# CLKB_main.net
KiCad netlist of a schematic drawn in Altium Designer
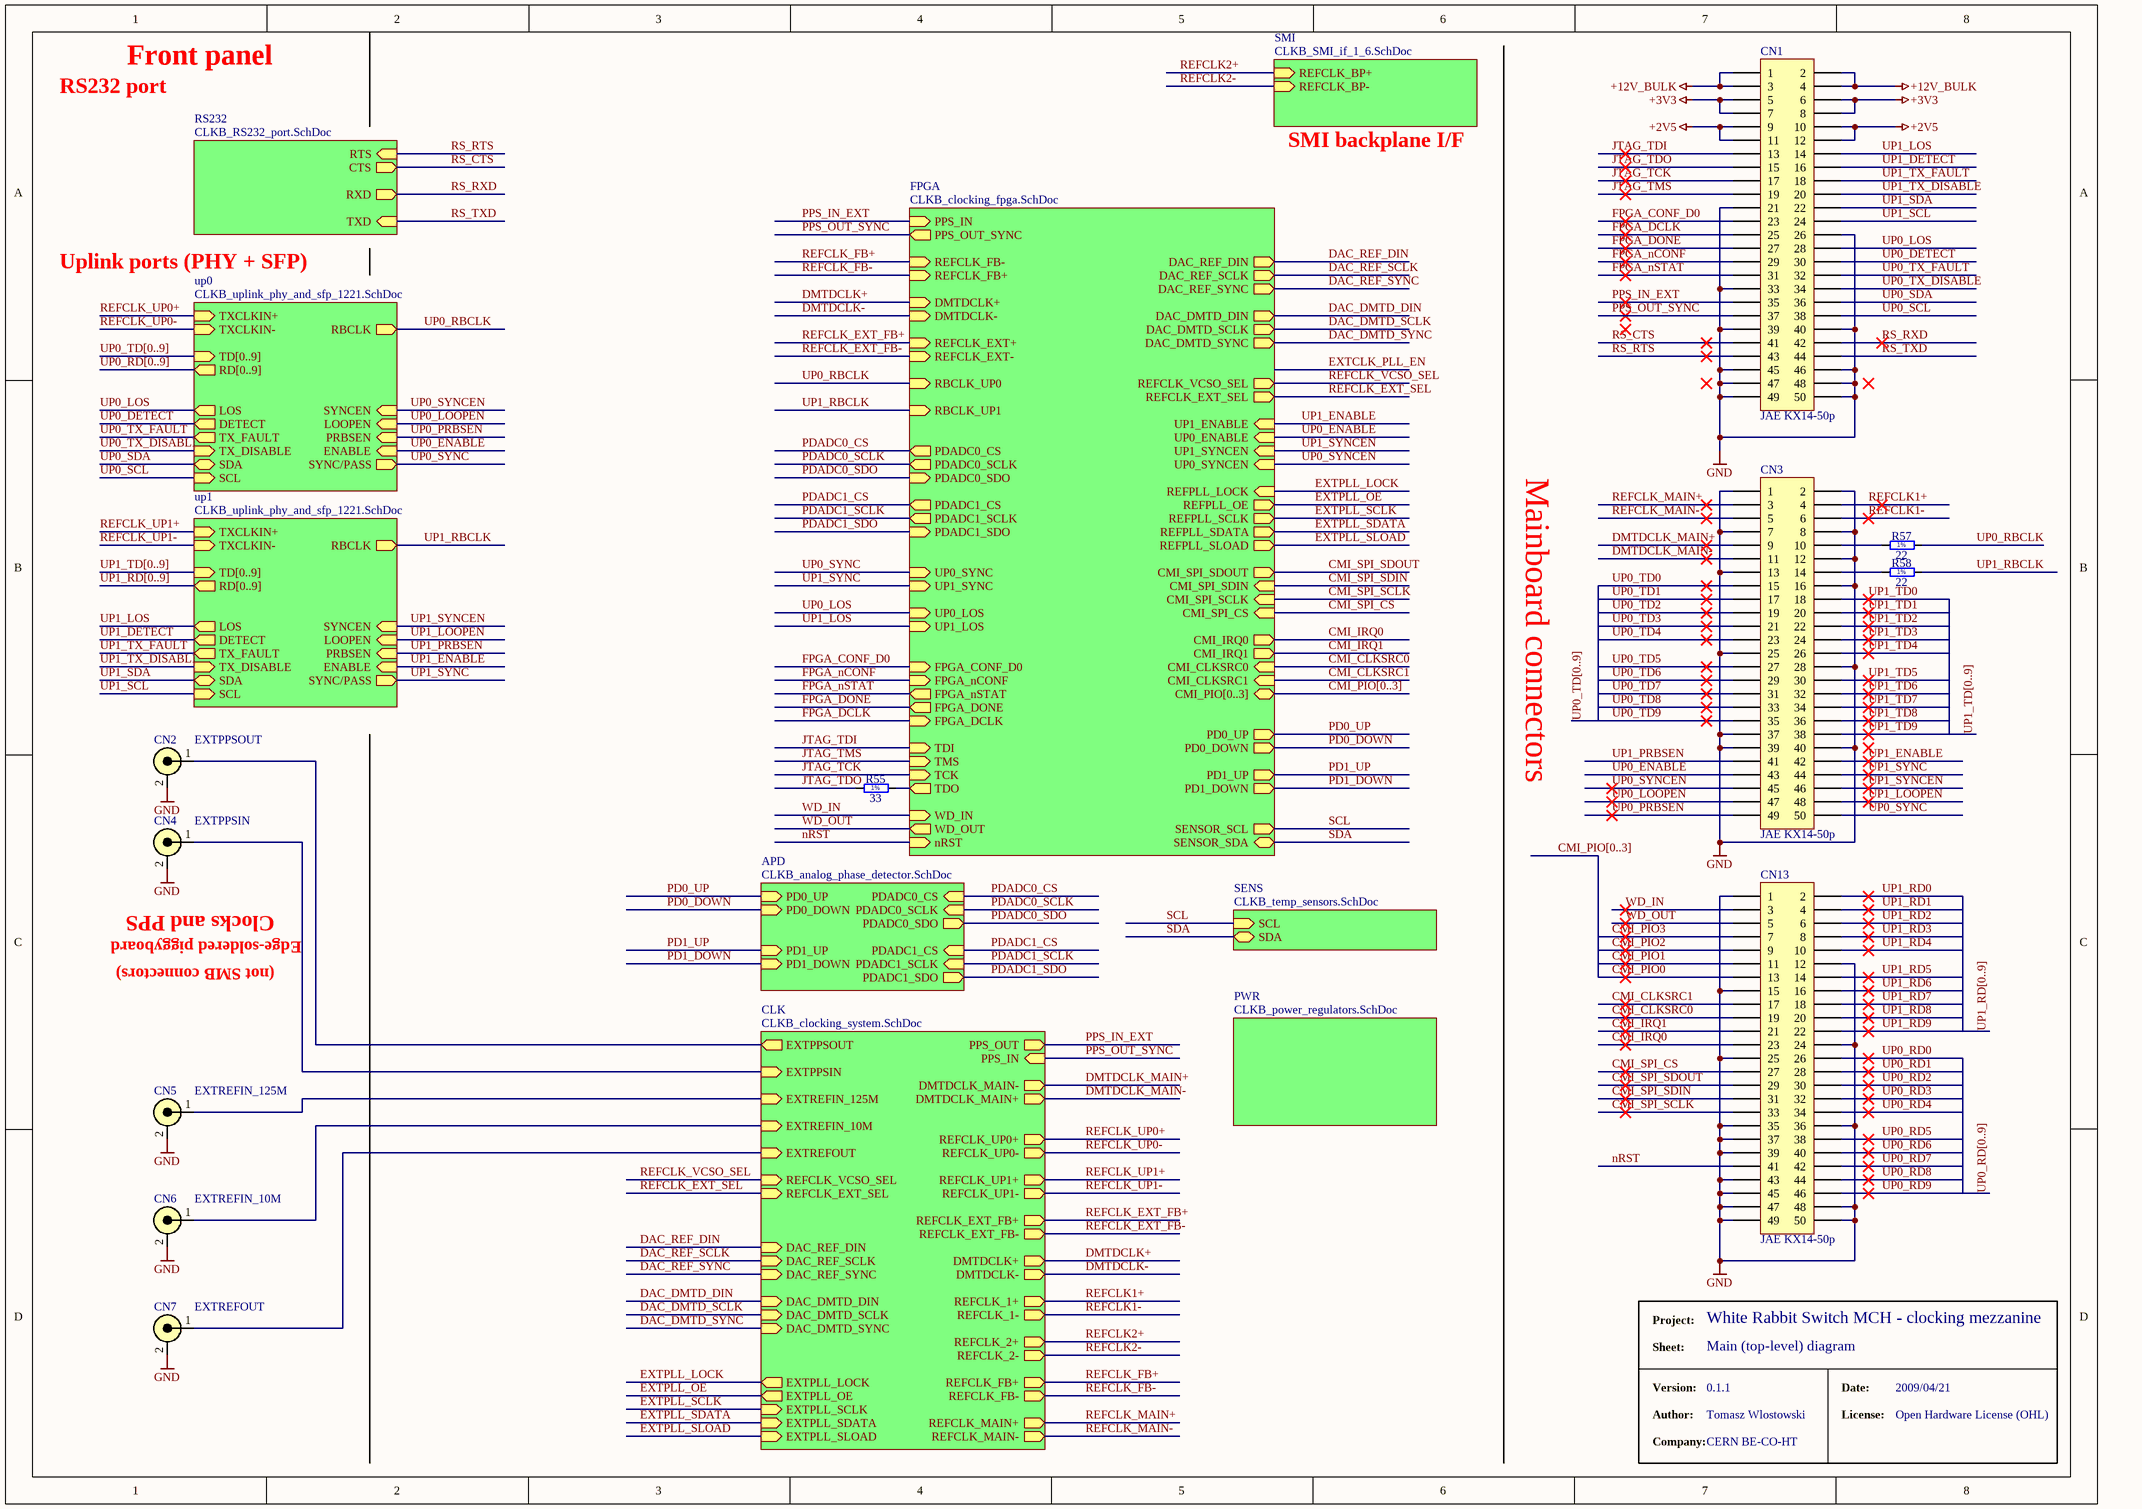
[diagram p0: CLKB_main.SchDoc]

(export (version "E")
  (design (tool "Eeschema 10.0.6"))
  (components
    (comp (ref "CN1")
      (value "JAE KX14-50p")
      (footprint "JAE_KX14_50P")
      (description "multipin B2B connector (plug)")
      (libsource (lib "wr_switch") (part "KX14_50p"))
    )
    (comp (ref "CN2")
      (value "EXTPPSOUT")
      (footprint "MCH_SPECIAL_FP_CLOCKS")
      (description "SMB piggyboard connection")
      (libsource (lib "wr_switch") (part "SMA_SOCKET"))
    )
    (comp (ref "CN3")
      (value "JAE KX14-50p")
      (footprint "JAE_KX14_50P")
      (description "multipin B2B connector (plug)")
      (libsource (lib "wr_switch") (part "KX14_50p"))
    )
    (comp (ref "CN4")
      (value "EXTPPSIN")
      (footprint "MCH_SPECIAL_FP_CLOCKS")
      (description "SMB piggyboard connection")
      (libsource (lib "wr_switch") (part "SMA_SOCKET"))
    )
    (comp (ref "CN5")
      (value "EXTREFIN_125M")
      (footprint "MCH_SPECIAL_FP_CLOCKS")
      (description "SMB piggyboard connection")
      (libsource (lib "wr_switch") (part "SMA_SOCKET"))
    )
    (comp (ref "CN6")
      (value "EXTREFIN_10M")
      (footprint "MCH_SPECIAL_FP_CLOCKS")
      (description "SMB piggyboard connection")
      (libsource (lib "wr_switch") (part "SMA_SOCKET"))
    )
    (comp (ref "CN7")
      (value "EXTREFOUT")
      (footprint "MCH_SPECIAL_FP_CLOCKS")
      (description "SMB piggyboard connection")
      (libsource (lib "wr_switch") (part "SMA_SOCKET"))
    )
    (comp (ref "CN13")
      (value "JAE KX14-50p")
      (footprint "JAE_KX14_50P")
      (description "multipin B2B connector (plug)")
      (libsource (lib "wr_switch") (part "KX14_50p"))
    )
    (comp (ref "R55")
      (value "33")
      (footprint "RESC1608X55N")
      (description "Resistor - 1%")
      (fields
        (field (name "PART NUMBER") "R0603_33R_1%_0.1W_100PPM")
        (field (name "POWER") "0.1W")
        (field (name "AUTHOR") "CERN DEM JLC")
      )
      (libsource (lib "Resistors") (part "Resistor - 1%"))
    )
    (comp (ref "R57")
      (value "22")
      (footprint "RESC1608X55N")
      (description "Resistor - 1%")
      (fields
        (field (name "PART NUMBER") "R0603_22R_1%_0.1W_100PPM")
        (field (name "POWER") "0.1W")
        (field (name "AUTHOR") "CERN DEM JLC")
      )
      (libsource (lib "Resistors") (part "Resistor - 1%"))
    )
    (comp (ref "R58")
      (value "22")
      (footprint "RESC1608X55N")
      (description "Resistor - 1%")
      (fields
        (field (name "PART NUMBER") "R0603_22R_1%_0.1W_100PPM")
        (field (name "POWER") "0.1W")
        (field (name "AUTHOR") "CERN DEM JLC")
      )
      (libsource (lib "Resistors") (part "Resistor - 1%"))
    )
  )
  (nets
    (net (code "1") (name "+2V5") (class "Default")
      (node (ref "CN1") (pin "10") (pinfunction "10_10") (pintype "passive"))
      (node (ref "CN1") (pin "11") (pinfunction "11_11") (pintype "passive"))
      (node (ref "CN1") (pin "12") (pinfunction "12_12") (pintype "passive"))
      (node (ref "CN1") (pin "9") (pinfunction "9_9") (pintype "passive"))
    )
    (net (code "2") (name "+3V3") (class "Default")
      (node (ref "CN1") (pin "5") (pinfunction "5_5") (pintype "passive"))
      (node (ref "CN1") (pin "6") (pinfunction "6_6") (pintype "passive"))
      (node (ref "CN1") (pin "7") (pinfunction "7_7") (pintype "passive"))
      (node (ref "CN1") (pin "8") (pinfunction "8_8") (pintype "passive"))
    )
    (net (code "3") (name "+12V_BULK") (class "Default")
      (node (ref "CN1") (pin "1") (pinfunction "1_1") (pintype "passive"))
      (node (ref "CN1") (pin "2") (pinfunction "2_2") (pintype "passive"))
      (node (ref "CN1") (pin "3") (pinfunction "3_3") (pintype "passive"))
      (node (ref "CN1") (pin "4") (pinfunction "4_4") (pintype "passive"))
    )
    (net (code "4") (name "/CMI_CLKSRC0") (class "Default")
      (node (ref "CN13") (pin "19") (pinfunction "19_19") (pintype "passive"))
    )
    (net (code "5") (name "/CMI_CLKSRC1") (class "Default")
      (node (ref "CN13") (pin "17") (pinfunction "17_17") (pintype "passive"))
    )
    (net (code "6") (name "/CMI_IRQ0") (class "Default")
      (node (ref "CN13") (pin "23") (pinfunction "23_23") (pintype "passive"))
    )
    (net (code "7") (name "/CMI_IRQ1") (class "Default")
      (node (ref "CN13") (pin "21") (pinfunction "21_21") (pintype "passive"))
    )
    (net (code "8") (name "/CMI_PIO0") (class "Default")
      (node (ref "CN13") (pin "13") (pinfunction "13_13") (pintype "passive"))
    )
    (net (code "9") (name "/CMI_PIO1") (class "Default")
      (node (ref "CN13") (pin "11") (pinfunction "11_11") (pintype "passive"))
    )
    (net (code "10") (name "/CMI_PIO2") (class "Default")
      (node (ref "CN13") (pin "9") (pinfunction "9_9") (pintype "passive"))
    )
    (net (code "11") (name "/CMI_PIO3") (class "Default")
      (node (ref "CN13") (pin "7") (pinfunction "7_7") (pintype "passive"))
    )
    (net (code "13") (name "/CMI_SPI_CS") (class "Default")
      (node (ref "CN13") (pin "27") (pinfunction "27_27") (pintype "passive"))
    )
    (net (code "14") (name "/CMI_SPI_SCLK") (class "Default")
      (node (ref "CN13") (pin "33") (pinfunction "33_33") (pintype "passive"))
    )
    (net (code "15") (name "/CMI_SPI_SDIN") (class "Default")
      (node (ref "CN13") (pin "31") (pinfunction "31_31") (pintype "passive"))
    )
    (net (code "16") (name "/CMI_SPI_SDOUT") (class "Default")
      (node (ref "CN13") (pin "29") (pinfunction "29_29") (pintype "passive"))
    )
    (net (code "25") (name "/DMTDCLK_MAIN+") (class "Default")
      (node (ref "CN3") (pin "9") (pinfunction "9_9") (pintype "passive"))
    )
    (net (code "26") (name "/DMTDCLK_MAIN-") (class "Default")
      (node (ref "CN3") (pin "11") (pinfunction "11_11") (pintype "passive"))
    )
    (net (code "33") (name "/EXTPPSIN") (class "Default")
      (node (ref "CN4") (pin "1") (pinfunction "HOT_1") (pintype "passive"))
    )
    (net (code "34") (name "/EXTPPSOUT") (class "Default")
      (node (ref "CN2") (pin "1") (pinfunction "HOT_1") (pintype "passive"))
    )
    (net (code "35") (name "/EXTREFIN_10M") (class "Default")
      (node (ref "CN6") (pin "1") (pinfunction "HOT_1") (pintype "passive"))
    )
    (net (code "36") (name "/EXTREFIN_125M") (class "Default")
      (node (ref "CN5") (pin "1") (pinfunction "HOT_1") (pintype "passive"))
    )
    (net (code "37") (name "/EXTREFOUT") (class "Default")
      (node (ref "CN7") (pin "1") (pinfunction "HOT_1") (pintype "passive"))
    )
    (net (code "38") (name "/FPGA_CONF_D0") (class "Default")
      (node (ref "CN1") (pin "23") (pinfunction "23_23") (pintype "passive"))
    )
    (net (code "39") (name "/FPGA_DCLK") (class "Default")
      (node (ref "CN1") (pin "25") (pinfunction "25_25") (pintype "passive"))
    )
    (net (code "40") (name "/FPGA_DONE") (class "Default")
      (node (ref "CN1") (pin "27") (pinfunction "27_27") (pintype "passive"))
    )
    (net (code "41") (name "/FPGA_nCONF") (class "Default")
      (node (ref "CN1") (pin "29") (pinfunction "29_29") (pintype "passive"))
    )
    (net (code "42") (name "/FPGA_nSTAT") (class "Default")
      (node (ref "CN1") (pin "31") (pinfunction "31_31") (pintype "passive"))
    )
    (net (code "43") (name "/JTAG_TCK") (class "Default")
      (node (ref "CN1") (pin "17") (pinfunction "17_17") (pintype "passive"))
    )
    (net (code "44") (name "/JTAG_TDI") (class "Default")
      (node (ref "CN1") (pin "13") (pinfunction "13_13") (pintype "passive"))
    )
    (net (code "45") (name "/JTAG_TDO") (class "Default")
      (node (ref "CN1") (pin "15") (pinfunction "15_15") (pintype "passive"))
      (node (ref "R55") (pin "1") (pinfunction "1_1") (pintype "passive"))
    )
    (net (code "46") (name "/JTAG_TMS") (class "Default")
      (node (ref "CN1") (pin "19") (pinfunction "19_19") (pintype "passive"))
    )
    (net (code "57") (name "/PPS_IN_EXT") (class "Default")
      (node (ref "CN1") (pin "35") (pinfunction "35_35") (pintype "passive"))
    )
    (net (code "58") (name "/PPS_OUT_SYNC") (class "Default")
      (node (ref "CN1") (pin "37") (pinfunction "37_37") (pintype "passive"))
    )
    (net (code "59") (name "/REFCLK1+") (class "Default")
      (node (ref "CN3") (pin "4") (pinfunction "4_4") (pintype "passive"))
    )
    (net (code "68") (name "/REFCLK1-") (class "Default")
      (node (ref "CN3") (pin "6") (pinfunction "6_6") (pintype "passive"))
    )
    (net (code "69") (name "/REFCLK_MAIN+") (class "Default")
      (node (ref "CN3") (pin "3") (pinfunction "3_3") (pintype "passive"))
    )
    (net (code "75") (name "/REFCLK_MAIN-") (class "Default")
      (node (ref "CN3") (pin "5") (pinfunction "5_5") (pintype "passive"))
    )
    (net (code "76") (name "/RS_CTS") (class "Default")
      (node (ref "CN1") (pin "41") (pinfunction "41_41") (pintype "passive"))
    )
    (net (code "78") (name "/RS_RTS") (class "Default")
      (node (ref "CN1") (pin "43") (pinfunction "43_43") (pintype "passive"))
    )
    (net (code "81") (name "/RS_RXD") (class "Default")
      (node (ref "CN1") (pin "42") (pinfunction "42_42") (pintype "passive"))
    )
    (net (code "82") (name "/RS_TXD") (class "Default")
      (node (ref "CN1") (pin "44") (pinfunction "44_44") (pintype "passive"))
    )
    (net (code "83") (name "/TDO") (class "Default")
      (node (ref "R55") (pin "2") (pinfunction "2_2") (pintype "passive"))
    )
    (net (code "85") (name "/UP0_DETECT") (class "Default")
      (node (ref "CN1") (pin "30") (pinfunction "30_30") (pintype "passive"))
    )
    (net (code "87") (name "/UP0_ENABLE") (class "Default")
      (node (ref "CN3") (pin "43") (pinfunction "43_43") (pintype "passive"))
    )
    (net (code "88") (name "/UP0_LOOPEN") (class "Default")
      (node (ref "CN3") (pin "47") (pinfunction "47_47") (pintype "passive"))
    )
    (net (code "89") (name "/UP0_LOS") (class "Default")
      (node (ref "CN1") (pin "28") (pinfunction "28_28") (pintype "passive"))
    )
    (net (code "90") (name "/UP0_PRBSEN") (class "Default")
      (node (ref "CN3") (pin "49") (pinfunction "49_49") (pintype "passive"))
    )
    (net (code "91") (name "/UP0_RBCLK") (class "Default")
      (node (ref "R57") (pin "2") (pinfunction "2_2") (pintype "passive"))
    )
    (net (code "92") (name "/UP0_RD0") (class "Default")
      (node (ref "CN13") (pin "26") (pinfunction "26_26") (pintype "passive"))
    )
    (net (code "93") (name "/UP0_RD1") (class "Default")
      (node (ref "CN13") (pin "28") (pinfunction "28_28") (pintype "passive"))
    )
    (net (code "94") (name "/UP0_RD2") (class "Default")
      (node (ref "CN13") (pin "30") (pinfunction "30_30") (pintype "passive"))
    )
    (net (code "95") (name "/UP0_RD3") (class "Default")
      (node (ref "CN13") (pin "32") (pinfunction "32_32") (pintype "passive"))
    )
    (net (code "96") (name "/UP0_RD4") (class "Default")
      (node (ref "CN13") (pin "34") (pinfunction "34_34") (pintype "passive"))
    )
    (net (code "97") (name "/UP0_RD5") (class "Default")
      (node (ref "CN13") (pin "38") (pinfunction "38_38") (pintype "passive"))
    )
    (net (code "99") (name "/UP0_RD6") (class "Default")
      (node (ref "CN13") (pin "40") (pinfunction "40_40") (pintype "passive"))
    )
    (net (code "100") (name "/UP0_RD7") (class "Default")
      (node (ref "CN13") (pin "42") (pinfunction "42_42") (pintype "passive"))
    )
    (net (code "101") (name "/UP0_RD8") (class "Default")
      (node (ref "CN13") (pin "44") (pinfunction "44_44") (pintype "passive"))
    )
    (net (code "103") (name "/UP0_RD9") (class "Default")
      (node (ref "CN13") (pin "46") (pinfunction "46_46") (pintype "passive"))
    )
    (net (code "104") (name "/UP0_SCL") (class "Default")
      (node (ref "CN1") (pin "38") (pinfunction "38_38") (pintype "passive"))
    )
    (net (code "105") (name "/UP0_SDA") (class "Default")
      (node (ref "CN1") (pin "36") (pinfunction "36_36") (pintype "passive"))
    )
    (net (code "106") (name "/UP0_SYNC") (class "Default")
      (node (ref "CN3") (pin "50") (pinfunction "50_50") (pintype "passive"))
    )
    (net (code "107") (name "/UP0_SYNCEN") (class "Default")
      (node (ref "CN3") (pin "45") (pinfunction "45_45") (pintype "passive"))
    )
    (net (code "108") (name "/UP0_TD0") (class "Default")
      (node (ref "CN3") (pin "15") (pinfunction "15_15") (pintype "passive"))
    )
    (net (code "109") (name "/UP0_TD1") (class "Default")
      (node (ref "CN3") (pin "17") (pinfunction "17_17") (pintype "passive"))
    )
    (net (code "110") (name "/UP0_TD2") (class "Default")
      (node (ref "CN3") (pin "19") (pinfunction "19_19") (pintype "passive"))
    )
    (net (code "111") (name "/UP0_TD3") (class "Default")
      (node (ref "CN3") (pin "21") (pinfunction "21_21") (pintype "passive"))
    )
    (net (code "112") (name "/UP0_TD4") (class "Default")
      (node (ref "CN3") (pin "23") (pinfunction "23_23") (pintype "passive"))
    )
    (net (code "114") (name "/UP0_TD5") (class "Default")
      (node (ref "CN3") (pin "27") (pinfunction "27_27") (pintype "passive"))
    )
    (net (code "115") (name "/UP0_TD6") (class "Default")
      (node (ref "CN3") (pin "29") (pinfunction "29_29") (pintype "passive"))
    )
    (net (code "116") (name "/UP0_TD7") (class "Default")
      (node (ref "CN3") (pin "31") (pinfunction "31_31") (pintype "passive"))
    )
    (net (code "119") (name "/UP0_TD8") (class "Default")
      (node (ref "CN3") (pin "33") (pinfunction "33_33") (pintype "passive"))
    )
    (net (code "120") (name "/UP0_TD9") (class "Default")
      (node (ref "CN3") (pin "35") (pinfunction "35_35") (pintype "passive"))
    )
    (net (code "121") (name "/UP0_TX_DISABLE") (class "Default")
      (node (ref "CN1") (pin "34") (pinfunction "34_34") (pintype "passive"))
    )
    (net (code "122") (name "/UP0_TX_FAULT") (class "Default")
      (node (ref "CN1") (pin "32") (pinfunction "32_32") (pintype "passive"))
    )
    (net (code "123") (name "/UP1_DETECT") (class "Default")
      (node (ref "CN1") (pin "16") (pinfunction "16_16") (pintype "passive"))
    )
    (net (code "124") (name "/UP1_ENABLE") (class "Default")
      (node (ref "CN3") (pin "42") (pinfunction "42_42") (pintype "passive"))
    )
    (net (code "125") (name "/UP1_LOOPEN") (class "Default")
      (node (ref "CN3") (pin "48") (pinfunction "48_48") (pintype "passive"))
    )
    (net (code "126") (name "/UP1_LOS") (class "Default")
      (node (ref "CN1") (pin "14") (pinfunction "14_14") (pintype "passive"))
    )
    (net (code "127") (name "/UP1_PRBSEN") (class "Default")
      (node (ref "CN3") (pin "41") (pinfunction "41_41") (pintype "passive"))
    )
    (net (code "128") (name "/UP1_RBCLK") (class "Default")
      (node (ref "R58") (pin "2") (pinfunction "2_2") (pintype "passive"))
    )
    (net (code "129") (name "/UP1_RD0") (class "Default")
      (node (ref "CN13") (pin "2") (pinfunction "2_2") (pintype "passive"))
    )
    (net (code "130") (name "/UP1_RD1") (class "Default")
      (node (ref "CN13") (pin "4") (pinfunction "4_4") (pintype "passive"))
    )
    (net (code "131") (name "/UP1_RD2") (class "Default")
      (node (ref "CN13") (pin "6") (pinfunction "6_6") (pintype "passive"))
    )
    (net (code "133") (name "/UP1_RD3") (class "Default")
      (node (ref "CN13") (pin "8") (pinfunction "8_8") (pintype "passive"))
    )
    (net (code "134") (name "/UP1_RD4") (class "Default")
      (node (ref "CN13") (pin "10") (pinfunction "10_10") (pintype "passive"))
    )
    (net (code "148") (name "/UP1_RD5") (class "Default")
      (node (ref "CN13") (pin "14") (pinfunction "14_14") (pintype "passive"))
    )
    (net (code "149") (name "/UP1_RD6") (class "Default")
      (node (ref "CN13") (pin "16") (pinfunction "16_16") (pintype "passive"))
    )
    (net (code "152") (name "/UP1_RD7") (class "Default")
      (node (ref "CN13") (pin "18") (pinfunction "18_18") (pintype "passive"))
    )
    (net (code "153") (name "/UP1_RD8") (class "Default")
      (node (ref "CN13") (pin "20") (pinfunction "20_20") (pintype "passive"))
    )
    (net (code "154") (name "/UP1_RD9") (class "Default")
      (node (ref "CN13") (pin "22") (pinfunction "22_22") (pintype "passive"))
    )
    (net (code "155") (name "/UP1_SCL") (class "Default")
      (node (ref "CN1") (pin "24") (pinfunction "24_24") (pintype "passive"))
    )
    (net (code "156") (name "/UP1_SDA") (class "Default")
      (node (ref "CN1") (pin "22") (pinfunction "22_22") (pintype "passive"))
    )
    (net (code "157") (name "/UP1_SYNC") (class "Default")
      (node (ref "CN3") (pin "44") (pinfunction "44_44") (pintype "passive"))
    )
    (net (code "158") (name "/UP1_SYNCEN") (class "Default")
      (node (ref "CN3") (pin "46") (pinfunction "46_46") (pintype "passive"))
    )
    (net (code "159") (name "/UP1_TD0") (class "Default")
      (node (ref "CN3") (pin "18") (pinfunction "18_18") (pintype "passive"))
    )
    (net (code "160") (name "/UP1_TD1") (class "Default")
      (node (ref "CN3") (pin "20") (pinfunction "20_20") (pintype "passive"))
    )
    (net (code "161") (name "/UP1_TD2") (class "Default")
      (node (ref "CN3") (pin "22") (pinfunction "22_22") (pintype "passive"))
    )
    (net (code "162") (name "/UP1_TD3") (class "Default")
      (node (ref "CN3") (pin "24") (pinfunction "24_24") (pintype "passive"))
    )
    (net (code "163") (name "/UP1_TD4") (class "Default")
      (node (ref "CN3") (pin "26") (pinfunction "26_26") (pintype "passive"))
    )
    (net (code "164") (name "/UP1_TD5") (class "Default")
      (node (ref "CN3") (pin "30") (pinfunction "30_30") (pintype "passive"))
    )
    (net (code "165") (name "/UP1_TD6") (class "Default")
      (node (ref "CN3") (pin "32") (pinfunction "32_32") (pintype "passive"))
    )
    (net (code "166") (name "/UP1_TD7") (class "Default")
      (node (ref "CN3") (pin "34") (pinfunction "34_34") (pintype "passive"))
    )
    (net (code "167") (name "/UP1_TD8") (class "Default")
      (node (ref "CN3") (pin "36") (pinfunction "36_36") (pintype "passive"))
    )
    (net (code "168") (name "/UP1_TD9") (class "Default")
      (node (ref "CN3") (pin "38") (pinfunction "38_38") (pintype "passive"))
    )
    (net (code "169") (name "/UP1_TX_DISABLE") (class "Default")
      (node (ref "CN1") (pin "20") (pinfunction "20_20") (pintype "passive"))
    )
    (net (code "170") (name "/UP1_TX_FAULT") (class "Default")
      (node (ref "CN1") (pin "18") (pinfunction "18_18") (pintype "passive"))
    )
    (net (code "171") (name "/WD_IN") (class "Default")
      (node (ref "CN13") (pin "3") (pinfunction "3_3") (pintype "passive"))
    )
    (net (code "172") (name "/WD_OUT") (class "Default")
      (node (ref "CN13") (pin "5") (pinfunction "5_5") (pintype "passive"))
    )
    (net (code "173") (name "/nRST") (class "Default")
      (node (ref "CN13") (pin "41") (pinfunction "41_41") (pintype "passive"))
    )
    (net (code "174") (name "GND") (class "Default")
      (node (ref "CN1") (pin "21") (pinfunction "21_21") (pintype "passive"))
      (node (ref "CN1") (pin "26") (pinfunction "26_26") (pintype "passive"))
      (node (ref "CN1") (pin "33") (pinfunction "33_33") (pintype "passive"))
      (node (ref "CN1") (pin "39") (pinfunction "39_39") (pintype "passive"))
      (node (ref "CN1") (pin "40") (pinfunction "40_40") (pintype "passive"))
      (node (ref "CN1") (pin "45") (pinfunction "45_45") (pintype "passive"))
      (node (ref "CN1") (pin "46") (pinfunction "46_46") (pintype "passive"))
      (node (ref "CN1") (pin "47") (pinfunction "47_47") (pintype "passive"))
      (node (ref "CN1") (pin "48") (pinfunction "48_48") (pintype "passive"))
      (node (ref "CN1") (pin "49") (pinfunction "49_49") (pintype "passive"))
      (node (ref "CN1") (pin "50") (pinfunction "50_50") (pintype "passive"))
      (node (ref "CN13") (pin "1") (pinfunction "1_1") (pintype "passive"))
      (node (ref "CN13") (pin "12") (pinfunction "12_12") (pintype "passive"))
      (node (ref "CN13") (pin "15") (pinfunction "15_15") (pintype "passive"))
      (node (ref "CN13") (pin "24") (pinfunction "24_24") (pintype "passive"))
      (node (ref "CN13") (pin "25") (pinfunction "25_25") (pintype "passive"))
      (node (ref "CN13") (pin "35") (pinfunction "35_35") (pintype "passive"))
      (node (ref "CN13") (pin "36") (pinfunction "36_36") (pintype "passive"))
      (node (ref "CN13") (pin "37") (pinfunction "37_37") (pintype "passive"))
      (node (ref "CN13") (pin "39") (pinfunction "39_39") (pintype "passive"))
      (node (ref "CN13") (pin "43") (pinfunction "43_43") (pintype "passive"))
      (node (ref "CN13") (pin "45") (pinfunction "45_45") (pintype "passive"))
      (node (ref "CN13") (pin "47") (pinfunction "47_47") (pintype "passive"))
      (node (ref "CN13") (pin "48") (pinfunction "48_48") (pintype "passive"))
      (node (ref "CN13") (pin "49") (pinfunction "49_49") (pintype "passive"))
      (node (ref "CN13") (pin "50") (pinfunction "50_50") (pintype "passive"))
      (node (ref "CN2") (pin "2") (pinfunction "GND_2") (pintype "passive"))
      (node (ref "CN3") (pin "1") (pinfunction "1_1") (pintype "passive"))
      (node (ref "CN3") (pin "12") (pinfunction "12_12") (pintype "passive"))
      (node (ref "CN3") (pin "13") (pinfunction "13_13") (pintype "passive"))
      (node (ref "CN3") (pin "16") (pinfunction "16_16") (pintype "passive"))
      (node (ref "CN3") (pin "2") (pinfunction "2_2") (pintype "passive"))
      (node (ref "CN3") (pin "25") (pinfunction "25_25") (pintype "passive"))
      (node (ref "CN3") (pin "28") (pinfunction "28_28") (pintype "passive"))
      (node (ref "CN3") (pin "37") (pinfunction "37_37") (pintype "passive"))
      (node (ref "CN3") (pin "39") (pinfunction "39_39") (pintype "passive"))
      (node (ref "CN3") (pin "40") (pinfunction "40_40") (pintype "passive"))
      (node (ref "CN3") (pin "7") (pinfunction "7_7") (pintype "passive"))
      (node (ref "CN3") (pin "8") (pinfunction "8_8") (pintype "passive"))
      (node (ref "CN4") (pin "2") (pinfunction "GND_2") (pintype "passive"))
      (node (ref "CN5") (pin "2") (pinfunction "GND_2") (pintype "passive"))
      (node (ref "CN6") (pin "2") (pinfunction "GND_2") (pintype "passive"))
      (node (ref "CN7") (pin "2") (pinfunction "GND_2") (pintype "passive"))
    )
    (net (code "175") (name "Net-(CN3-Pad10)") (class "Default")
      (node (ref "CN3") (pin "10") (pinfunction "10_10") (pintype "passive"))
      (node (ref "R57") (pin "1") (pinfunction "1_1") (pintype "passive"))
    )
    (net (code "176") (name "Net-(CN3-Pad14)") (class "Default")
      (node (ref "CN3") (pin "14") (pinfunction "14_14") (pintype "passive"))
      (node (ref "R58") (pin "1") (pinfunction "1_1") (pintype "passive"))
    )
  )
)
